# MateLightScrewCap.net
KiCad netlist of a schematic drawn in EAGLE
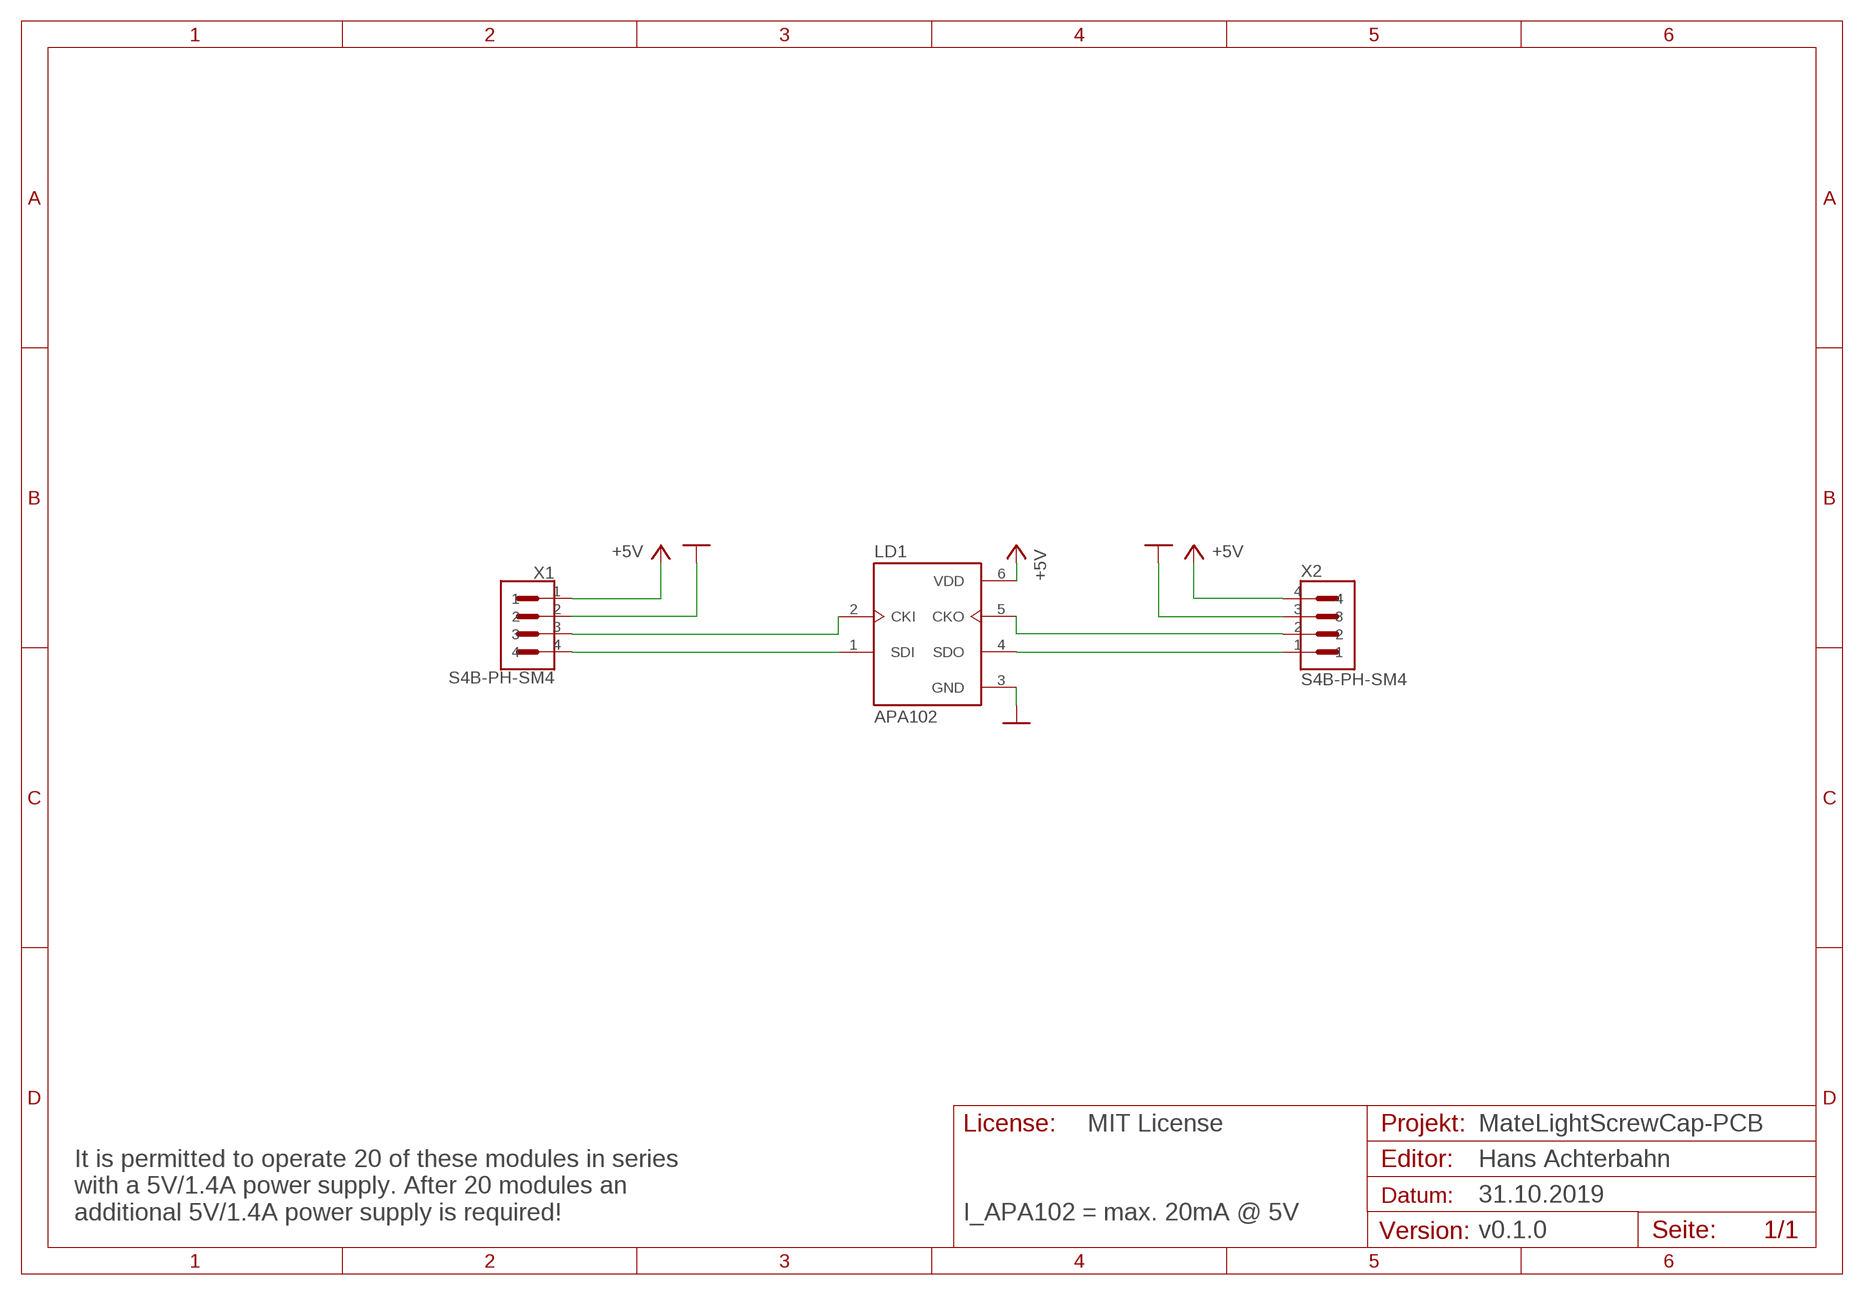
[diagram p0: schematic, sheet 1]

(export (version "E")
  (design (tool "Eeschema 10.0.6"))
  (components
    (comp (ref "LD1")
      (value "APA102")
      (footprint "eagle-import:APA102C-5050")
      (libsource (lib "eagle-import") (part "APA102APA102C-5050"))
    )
    (comp (ref "X1")
      (value "S4B-PH-SM4")
      (footprint "eagle-import:JST_S4B-PH-SM4-TB")
      (fields (field (name "MF") "JST Sales"))
      (libsource (lib "eagle-import") (part "S4B-PH-SM4-TB"))
    )
    (comp (ref "X2")
      (value "S4B-PH-SM4")
      (footprint "eagle-import:JST_S4B-PH-SM4-TB")
      (fields (field (name "MF") "JST Sales"))
      (libsource (lib "eagle-import") (part "S4B-PH-SM4-TB"))
    )
  )
  (nets
    (net (code "1") (name "+5V") (class "Default")
      (node (ref "LD1") (pin "6") (pinfunction "VDD_6") (pintype "power_in"))
      (node (ref "X1") (pin "1") (pinfunction "1_1") (pintype "passive"))
      (node (ref "X2") (pin "4") (pinfunction "4_4") (pintype "passive"))
    )
    (net (code "2") (name "GND") (class "Default")
      (node (ref "LD1") (pin "3") (pinfunction "GND_3") (pintype "power_in"))
      (node (ref "X1") (pin "2") (pinfunction "2_2") (pintype "passive"))
      (node (ref "X2") (pin "3") (pinfunction "3_3") (pintype "passive"))
    )
    (net (code "3") (name "Net-(LD1-CKI)") (class "Default")
      (node (ref "LD1") (pin "2") (pinfunction "CKI_2") (pintype "input"))
      (node (ref "X1") (pin "3") (pinfunction "3_3") (pintype "passive"))
    )
    (net (code "4") (name "Net-(LD1-CKO)") (class "Default")
      (node (ref "LD1") (pin "5") (pinfunction "CKO_5") (pintype "output"))
      (node (ref "X2") (pin "2") (pinfunction "2_2") (pintype "passive"))
    )
    (net (code "5") (name "Net-(LD1-SDI)") (class "Default")
      (node (ref "LD1") (pin "1") (pinfunction "SDI_1") (pintype "input"))
      (node (ref "X1") (pin "4") (pinfunction "4_4") (pintype "passive"))
    )
    (net (code "6") (name "Net-(LD1-SDO)") (class "Default")
      (node (ref "LD1") (pin "4") (pinfunction "SDO_4") (pintype "output"))
      (node (ref "X2") (pin "1") (pinfunction "1_1") (pintype "passive"))
    )
  )
)
